# keyBoard.net
KiCad netlist of a schematic drawn in EAGLE
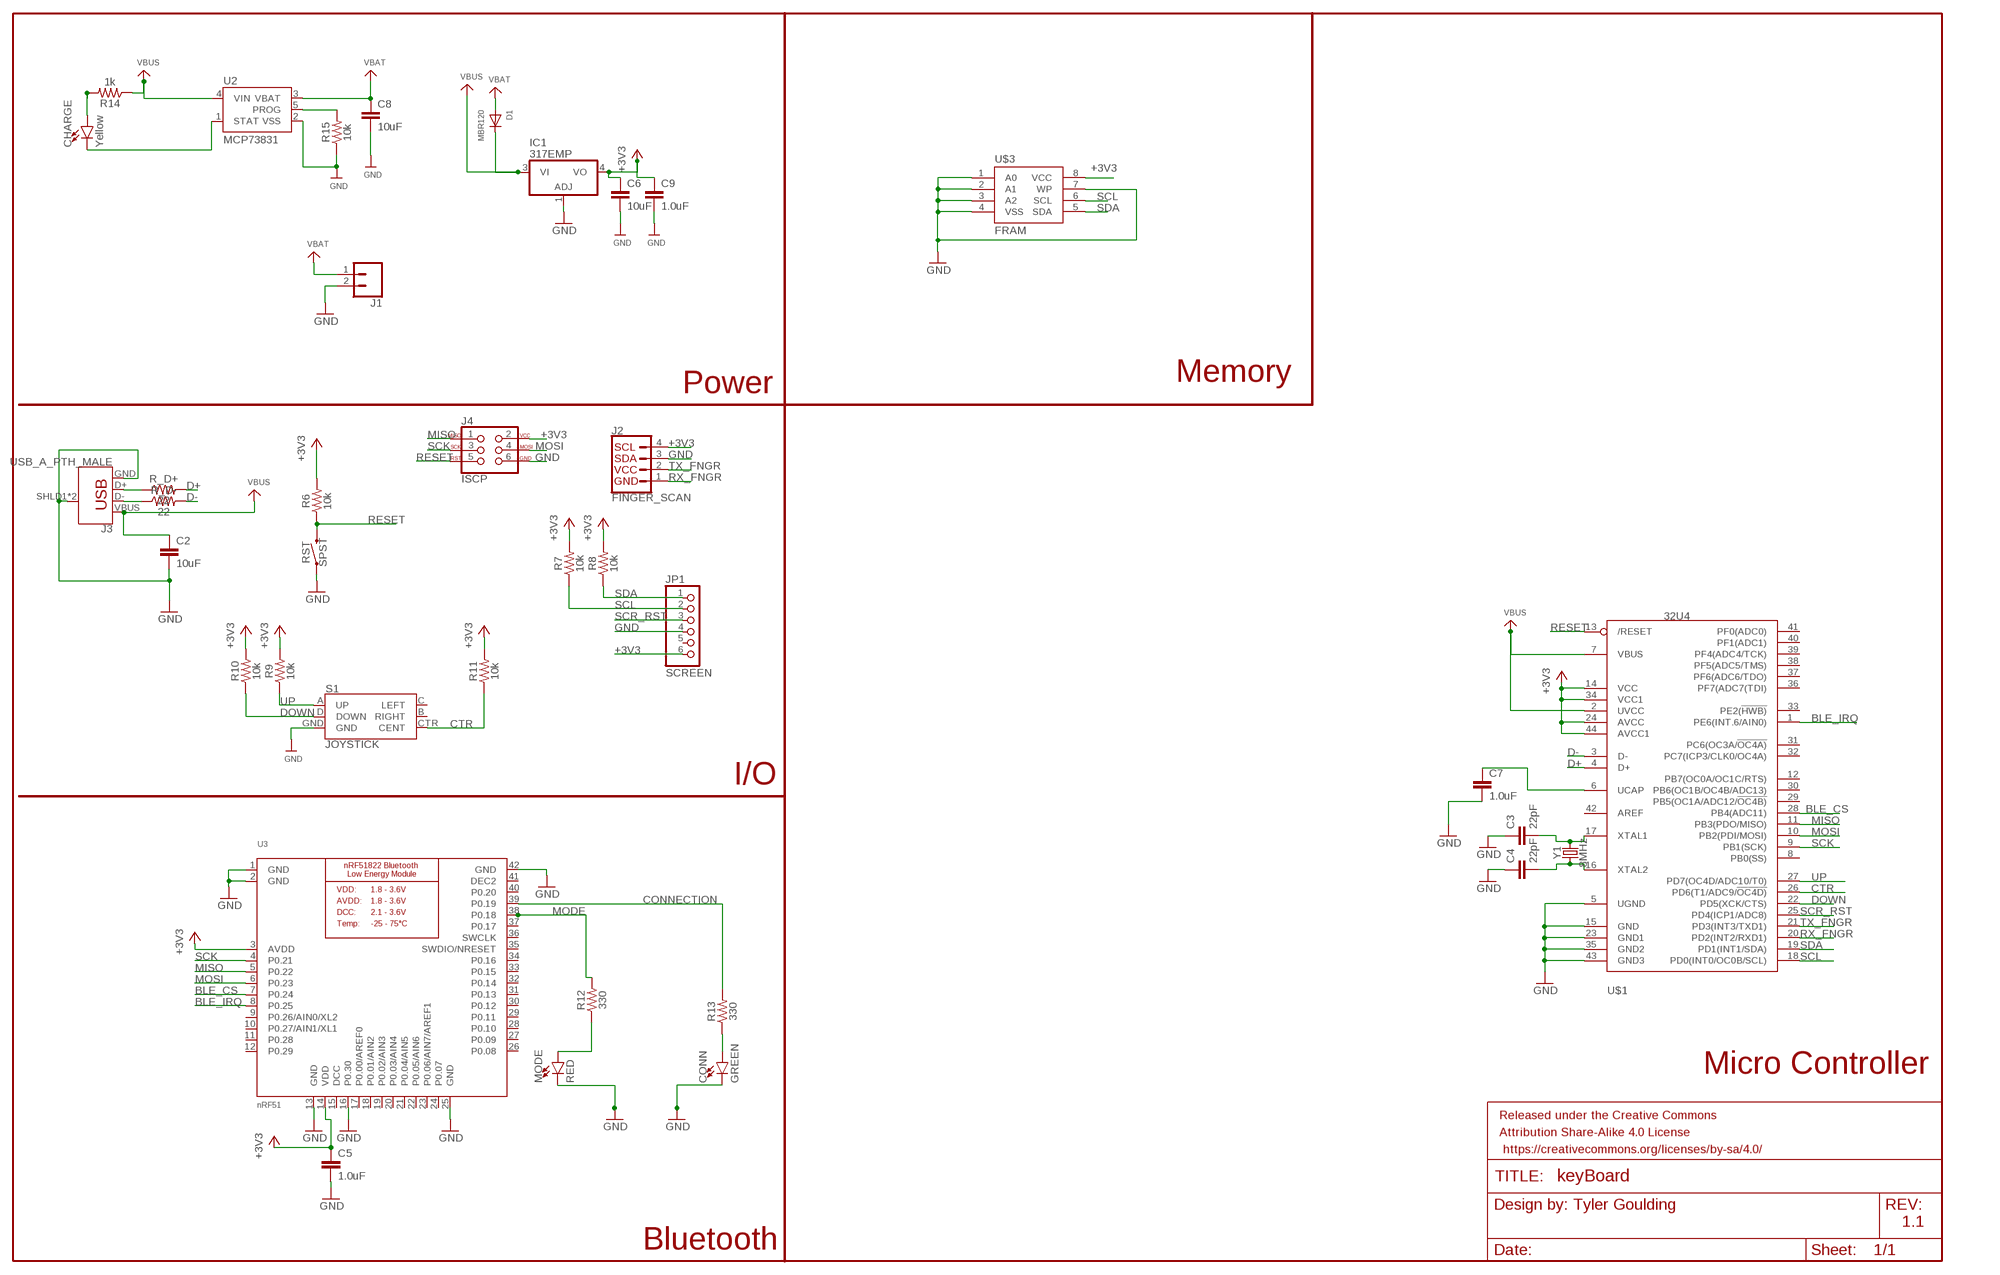
[diagram p0: schematic, sheet 1]

(export (version "E")
  (design (tool "Eeschema 10.0.6"))
  (components
    (comp (ref "C2")
      (value "10uF")
      (footprint "eagle-import:0603")
      (libsource (lib "eagle-import") (part "10UF-0603-6.3V-20%"))
    )
    (comp (ref "C3")
      (value "22pF")
      (footprint "eagle-import:0603")
      (libsource (lib "eagle-import") (part "22PF-0603-50V-5%"))
    )
    (comp (ref "C4")
      (value "22pF")
      (footprint "eagle-import:0603")
      (libsource (lib "eagle-import") (part "22PF-0603-50V-5%"))
    )
    (comp (ref "C5")
      (value "1.0uF")
      (footprint "eagle-import:0603")
      (libsource (lib "eagle-import") (part "1.0UF-0603-16V-10%"))
    )
    (comp (ref "C6")
      (value "10uF")
      (footprint "eagle-import:0603")
      (libsource (lib "eagle-import") (part "10UF-0603-6.3V-20%"))
    )
    (comp (ref "C7")
      (value "1.0uF")
      (footprint "eagle-import:0603")
      (libsource (lib "eagle-import") (part "1.0UF-0603-16V-10%"))
    )
    (comp (ref "C8")
      (value "10uF")
      (footprint "eagle-import:0603")
      (libsource (lib "eagle-import") (part "10UF-0603-6.3V-20%"))
    )
    (comp (ref "C9")
      (value "1.0uF")
      (footprint "eagle-import:0603")
      (libsource (lib "eagle-import") (part "1.0UF-0603-16V-10%"))
    )
    (comp (ref "CHARGE")
      (value "Yellow")
      (footprint "eagle-import:LED-0603")
      (libsource (lib "eagle-import") (part "LED-YELLOW0603"))
    )
    (comp (ref "CONN")
      (value "GREEN")
      (footprint "eagle-import:LED-0603")
      (libsource (lib "eagle-import") (part "LED-GREEN0603"))
    )
    (comp (ref "D1")
      (value "MBR120")
      (footprint "eagle-import:SOD-123FL")
      (libsource (lib "eagle-import") (part "DIODE_SOD-123FL"))
    )
    (comp (ref "FRAME1")
      (value "FRAME-LEDGER")
      (footprint "eagle-import:CREATIVE_COMMONS")
      (libsource (lib "eagle-import") (part "FRAME-LEDGER"))
    )
    (comp (ref "IC1")
      (value "317EMP")
      (footprint "eagle-import:SOT223")
      (libsource (lib "eagle-import") (part "317EMP"))
    )
    (comp (ref "J1")
      (value "CONN_02JST-PTH-2")
      (footprint "eagle-import:JST-2-PTH")
      (libsource (lib "eagle-import") (part "CONN_02JST-PTH-2"))
    )
    (comp (ref "J2")
      (value "FINGER_SCAN")
      (footprint "eagle-import:1X04_1MM_RA")
      (libsource (lib "eagle-import") (part "QWIIC_CONNECTORJS-1MM"))
    )
    (comp (ref "J3")
      (value "USB_A_PTH_MALE")
      (footprint "eagle-import:USB-A-H")
      (libsource (lib "eagle-import") (part "USB_A_PTH_MALE"))
    )
    (comp (ref "J4")
      (value "ISCP")
      (footprint "eagle-import:2X3-NS")
      (libsource (lib "eagle-import") (part "AVR_SPI_PROG_3X2NS"))
    )
    (comp (ref "JP1")
      (value "SCREEN")
      (footprint "eagle-import:1X06_ROUND")
      (libsource (lib "eagle-import") (part "HEADER-1X6ROUND"))
    )
    (comp (ref "MODE")
      (value "RED")
      (footprint "eagle-import:LED-0603")
      (libsource (lib "eagle-import") (part "LED-RED0603"))
    )
    (comp (ref "R6")
      (value "10k")
      (footprint "eagle-import:0603")
      (libsource (lib "eagle-import") (part "10KOHM-0603-1/10W-1%"))
    )
    (comp (ref "R7")
      (value "10k")
      (footprint "eagle-import:0603")
      (libsource (lib "eagle-import") (part "10KOHM-0603-1/10W-1%"))
    )
    (comp (ref "R8")
      (value "10k")
      (footprint "eagle-import:0603")
      (libsource (lib "eagle-import") (part "10KOHM-0603-1/10W-1%"))
    )
    (comp (ref "R9")
      (value "10k")
      (footprint "eagle-import:0603")
      (libsource (lib "eagle-import") (part "10KOHM-0603-1/10W-1%"))
    )
    (comp (ref "R10")
      (value "10k")
      (footprint "eagle-import:0603")
      (libsource (lib "eagle-import") (part "10KOHM-0603-1/10W-1%"))
    )
    (comp (ref "R11")
      (value "10k")
      (footprint "eagle-import:0603")
      (libsource (lib "eagle-import") (part "10KOHM-0603-1/10W-1%"))
    )
    (comp (ref "R12")
      (value "330")
      (footprint "eagle-import:0603")
      (libsource (lib "eagle-import") (part "330OHM-0603-1/10W-1%"))
    )
    (comp (ref "R13")
      (value "330")
      (footprint "eagle-import:0603")
      (libsource (lib "eagle-import") (part "330OHM-0603-1/10W-1%"))
    )
    (comp (ref "R14")
      (value "1k")
      (footprint "eagle-import:0603")
      (libsource (lib "eagle-import") (part "1KOHM-0603-1/10W-1%"))
    )
    (comp (ref "R15")
      (value "10k")
      (footprint "eagle-import:0603")
      (libsource (lib "eagle-import") (part "10KOHM-0603-1/10W-1%"))
    )
    (comp (ref "RST")
      (value "SPST")
      (footprint "eagle-import:TACTILE_SWITCH_SMD_4.5MM")
      (libsource (lib "eagle-import") (part "MOMENTARY-SWITCH-SPST-SMD-4.5MM"))
    )
    (comp (ref "R_D+")
      (value "22")
      (footprint "eagle-import:0603")
      (libsource (lib "eagle-import") (part "22OHM-0603-1/10W-1%"))
    )
    (comp (ref "R_D-")
      (value "22")
      (footprint "eagle-import:0603")
      (libsource (lib "eagle-import") (part "22OHM-0603-1/10W-1%"))
    )
    (comp (ref "S1")
      (value "JOYSTICK")
      (footprint "eagle-import:JOYSTICK_MINI")
      (libsource (lib "eagle-import") (part "JOYSTICK_MINI"))
    )
    (comp (ref "U$1")
      (value "32U4")
      (footprint "eagle-import:TQFP44")
      (libsource (lib "eagle-import") (part "ATMEGA32U4-AU"))
    )
    (comp (ref "U$3")
      (value "FRAM")
      (footprint "eagle-import:SOIC8")
      (libsource (lib "eagle-import") (part "FRAM"))
    )
    (comp (ref "U2")
      (value "MCP73831")
      (footprint "eagle-import:SOT23-5")
      (libsource (lib "eagle-import") (part "MCP73831"))
    )
    (comp (ref "U3")
      (value "nRF51")
      (footprint "eagle-import:BLE_MODULE_RAYTAC_MDBT40")
      (libsource (lib "eagle-import") (part "NRF51822_MODULE_MDBT40"))
    )
    (comp (ref "Y1")
      (value "8MHz")
      (footprint "eagle-import:CRYSTAL-SMD-5X3.2-4PAD")
      (libsource (lib "eagle-import") (part "CRYSTAL-8MHZSMD-5X3.2"))
    )
  )
  (nets
    (net (code "1") (name "+3V3") (class "Default")
      (node (ref "C5") (pin "1") (pinfunction "1_1") (pintype "passive"))
      (node (ref "C6") (pin "1") (pinfunction "1_1") (pintype "passive"))
      (node (ref "C9") (pin "1") (pinfunction "1_1") (pintype "passive"))
      (node (ref "IC1") (pin "4") (pinfunction "VO_4") (pintype "passive"))
      (node (ref "J2") (pin "4") (pinfunction "SCL_4") (pintype "passive"))
      (node (ref "J4") (pin "2") (pinfunction "2_2") (pintype "passive"))
      (node (ref "JP1") (pin "6") (pinfunction "6_6") (pintype "passive"))
      (node (ref "R10") (pin "2") (pinfunction "2_2") (pintype "passive"))
      (node (ref "R11") (pin "2") (pinfunction "2_2") (pintype "passive"))
      (node (ref "R6") (pin "2") (pinfunction "2_2") (pintype "passive"))
      (node (ref "R7") (pin "2") (pinfunction "2_2") (pintype "passive"))
      (node (ref "R8") (pin "2") (pinfunction "2_2") (pintype "passive"))
      (node (ref "R9") (pin "2") (pinfunction "2_2") (pintype "passive"))
      (node (ref "U$1") (pin "14") (pinfunction "VCC_14") (pintype "bidirectional"))
      (node (ref "U$1") (pin "24") (pinfunction "AVCC_24") (pintype "bidirectional"))
      (node (ref "U$1") (pin "34") (pinfunction "VCC1_34") (pintype "bidirectional"))
      (node (ref "U$1") (pin "44") (pinfunction "AVCC1_44") (pintype "bidirectional"))
      (node (ref "U$3") (pin "8") (pinfunction "VCC_8") (pintype "power_in"))
      (node (ref "U3") (pin "14") (pinfunction "VDD_14") (pintype "power_in"))
      (node (ref "U3") (pin "3") (pinfunction "AVDD_3") (pintype "power_in"))
    )
    (net (code "2") (name "/BLE_CS") (class "Default")
      (node (ref "U$1") (pin "28") (pinfunction "PB4(ADC11)_28") (pintype "bidirectional"))
      (node (ref "U3") (pin "7") (pinfunction "P0.24_7") (pintype "bidirectional"))
    )
    (net (code "3") (name "/BLE_IRQ") (class "Default")
      (node (ref "U$1") (pin "1") (pinfunction "PE6(INT.6/AIN0)_1") (pintype "bidirectional"))
      (node (ref "U3") (pin "8") (pinfunction "P0.25_8") (pintype "bidirectional"))
    )
    (net (code "4") (name "/CONNECTION") (class "Default")
      (node (ref "R13") (pin "2") (pinfunction "2_2") (pintype "passive"))
      (node (ref "U3") (pin "39") (pinfunction "P0.19_39") (pintype "bidirectional"))
    )
    (net (code "5") (name "/CTR") (class "Default")
      (node (ref "R11") (pin "1") (pinfunction "1_1") (pintype "passive"))
      (node (ref "S1") (pin "CTR") (pinfunction "CENT_CTR") (pintype "bidirectional"))
      (node (ref "U$1") (pin "26") (pinfunction "PD6(T1/ADC9/~{OC4D})_26") (pintype "bidirectional"))
    )
    (net (code "6") (name "/D+") (class "Default")
      (node (ref "R_D+") (pin "2") (pinfunction "2_2") (pintype "passive"))
      (node (ref "U$1") (pin "4") (pinfunction "D+_4") (pintype "bidirectional"))
    )
    (net (code "7") (name "/D-") (class "Default")
      (node (ref "R_D-") (pin "2") (pinfunction "2_2") (pintype "passive"))
      (node (ref "U$1") (pin "3") (pinfunction "D-_3") (pintype "bidirectional"))
    )
    (net (code "8") (name "/DCC") (class "Default")
      (node (ref "U3") (pin "15") (pinfunction "DCC_15") (pintype "power_in"))
    )
    (net (code "9") (name "/DEC2") (class "Default")
      (node (ref "U3") (pin "41") (pinfunction "DEC2_41") (pintype "power_in"))
    )
    (net (code "10") (name "/DOWN") (class "Default")
      (node (ref "R10") (pin "1") (pinfunction "1_1") (pintype "passive"))
      (node (ref "S1") (pin "D") (pinfunction "DOWN_D") (pintype "bidirectional"))
      (node (ref "U$1") (pin "22") (pinfunction "PD5(XCK/CTS)_22") (pintype "bidirectional"))
    )
    (net (code "11") (name "/MISO") (class "Default")
      (node (ref "J4") (pin "1") (pinfunction "1_1") (pintype "passive"))
      (node (ref "U$1") (pin "11") (pinfunction "PB3(PDO/MISO)_11") (pintype "bidirectional"))
      (node (ref "U3") (pin "5") (pinfunction "P0.22_5") (pintype "bidirectional"))
    )
    (net (code "12") (name "/MODE") (class "Default")
      (node (ref "R12") (pin "2") (pinfunction "2_2") (pintype "passive"))
      (node (ref "U3") (pin "38") (pinfunction "P0.18_38") (pintype "bidirectional"))
    )
    (net (code "13") (name "/MOSI") (class "Default")
      (node (ref "J4") (pin "4") (pinfunction "4_4") (pintype "passive"))
      (node (ref "U$1") (pin "10") (pinfunction "PB2(PDI/MOSI)_10") (pintype "bidirectional"))
      (node (ref "U3") (pin "6") (pinfunction "P0.23_6") (pintype "bidirectional"))
    )
    (net (code "14") (name "/RESET") (class "Default")
      (node (ref "J4") (pin "5") (pinfunction "5_5") (pintype "passive"))
      (node (ref "R6") (pin "1") (pinfunction "1_1") (pintype "passive"))
      (node (ref "RST") (pin "1") (pinfunction "2_1") (pintype "passive"))
      (node (ref "RST") (pin "4") (pinfunction "2_4") (pintype "passive"))
      (node (ref "U$1") (pin "13") (pinfunction "/RESET_13") (pintype "bidirectional"))
    )
    (net (code "15") (name "/RX_FNGR") (class "Default")
      (node (ref "J2") (pin "1") (pinfunction "GND_1") (pintype "power_in"))
      (node (ref "U$1") (pin "20") (pinfunction "PD2(INT2/RXD1)_20") (pintype "bidirectional"))
    )
    (net (code "16") (name "/SCK") (class "Default")
      (node (ref "J4") (pin "3") (pinfunction "3_3") (pintype "passive"))
      (node (ref "U$1") (pin "9") (pinfunction "PB1(SCK)_9") (pintype "bidirectional"))
      (node (ref "U3") (pin "4") (pinfunction "P0.21_4") (pintype "bidirectional"))
    )
    (net (code "17") (name "/SCL") (class "Default")
      (node (ref "JP1") (pin "2") (pinfunction "2_2") (pintype "passive"))
      (node (ref "R7") (pin "1") (pinfunction "1_1") (pintype "passive"))
      (node (ref "U$1") (pin "18") (pinfunction "PD0(INT0/OC0B/SCL)_18") (pintype "bidirectional"))
      (node (ref "U$3") (pin "6") (pinfunction "SCL_6") (pintype "bidirectional"))
    )
    (net (code "18") (name "/SCR_RST") (class "Default")
      (node (ref "JP1") (pin "3") (pinfunction "3_3") (pintype "passive"))
      (node (ref "U$1") (pin "25") (pinfunction "PD4(ICP1/ADC8)_25") (pintype "bidirectional"))
    )
    (net (code "19") (name "/SDA") (class "Default")
      (node (ref "JP1") (pin "1") (pinfunction "1_1") (pintype "passive"))
      (node (ref "R8") (pin "1") (pinfunction "1_1") (pintype "passive"))
      (node (ref "U$1") (pin "19") (pinfunction "PD1(INT1/SDA)_19") (pintype "bidirectional"))
      (node (ref "U$3") (pin "5") (pinfunction "SDA_5") (pintype "bidirectional"))
    )
    (net (code "20") (name "/TX_FNGR") (class "Default")
      (node (ref "J2") (pin "2") (pinfunction "VCC_2") (pintype "power_in"))
      (node (ref "U$1") (pin "21") (pinfunction "PD3(INT3/TXD1)_21") (pintype "bidirectional"))
    )
    (net (code "21") (name "/UP") (class "Default")
      (node (ref "R9") (pin "1") (pinfunction "1_1") (pintype "passive"))
      (node (ref "S1") (pin "A") (pinfunction "UP_A") (pintype "bidirectional"))
      (node (ref "U$1") (pin "27") (pinfunction "PD7(OC4D/ADC10/T0)_27") (pintype "bidirectional"))
    )
    (net (code "22") (name "GND") (class "Default")
      (node (ref "C2") (pin "2") (pinfunction "2_2") (pintype "passive"))
      (node (ref "C3") (pin "1") (pinfunction "1_1") (pintype "passive"))
      (node (ref "C4") (pin "1") (pinfunction "1_1") (pintype "passive"))
      (node (ref "C5") (pin "2") (pinfunction "2_2") (pintype "passive"))
      (node (ref "C6") (pin "2") (pinfunction "2_2") (pintype "passive"))
      (node (ref "C7") (pin "2") (pinfunction "2_2") (pintype "passive"))
      (node (ref "C8") (pin "2") (pinfunction "2_2") (pintype "passive"))
      (node (ref "C9") (pin "2") (pinfunction "2_2") (pintype "passive"))
      (node (ref "CONN") (pin "C") (pinfunction "C_C") (pintype "passive"))
      (node (ref "IC1") (pin "1") (pinfunction "ADJ_1") (pintype "input"))
      (node (ref "J1") (pin "2") (pinfunction "2_2") (pintype "passive"))
      (node (ref "J2") (pin "3") (pinfunction "SDA_3") (pintype "passive"))
      (node (ref "J3") (pin "GND") (pinfunction "GND_GND") (pintype "power_in"))
      (node (ref "J3") (pin "SHLD1") (pinfunction "SHIELD_SHLD1") (pintype "bidirectional"))
      (node (ref "J3") (pin "SHLD2") (pinfunction "SHIELD_SHLD2") (pintype "bidirectional"))
      (node (ref "J4") (pin "6") (pinfunction "6_6") (pintype "passive"))
      (node (ref "JP1") (pin "4") (pinfunction "4_4") (pintype "passive"))
      (node (ref "MODE") (pin "C") (pinfunction "C_C") (pintype "passive"))
      (node (ref "R15") (pin "1") (pinfunction "1_1") (pintype "passive"))
      (node (ref "RST") (pin "2") (pinfunction "1_2") (pintype "passive"))
      (node (ref "RST") (pin "3") (pinfunction "1_3") (pintype "passive"))
      (node (ref "S1") (pin "GND") (pinfunction "GND_GND") (pintype "bidirectional"))
      (node (ref "U$1") (pin "15") (pinfunction "GND_15") (pintype "bidirectional"))
      (node (ref "U$1") (pin "23") (pinfunction "GND1_23") (pintype "bidirectional"))
      (node (ref "U$1") (pin "35") (pinfunction "GND2_35") (pintype "bidirectional"))
      (node (ref "U$1") (pin "43") (pinfunction "GND3_43") (pintype "bidirectional"))
      (node (ref "U$1") (pin "5") (pinfunction "UGND_5") (pintype "bidirectional"))
      (node (ref "U$3") (pin "1") (pinfunction "A0_1") (pintype "bidirectional"))
      (node (ref "U$3") (pin "2") (pinfunction "A1_2") (pintype "bidirectional"))
      (node (ref "U$3") (pin "3") (pinfunction "A2_3") (pintype "bidirectional"))
      (node (ref "U$3") (pin "4") (pinfunction "VSS_4") (pintype "power_in"))
      (node (ref "U$3") (pin "7") (pinfunction "WP_7") (pintype "bidirectional"))
      (node (ref "U2") (pin "2") (pinfunction "VSS_2") (pintype "power_in"))
      (node (ref "U3") (pin "1") (pinfunction "GND_1") (pintype "power_in"))
      (node (ref "U3") (pin "13") (pinfunction "GND_13") (pintype "power_in"))
      (node (ref "U3") (pin "16") (pinfunction "P0.30_16") (pintype "bidirectional"))
      (node (ref "U3") (pin "2") (pinfunction "GND_2") (pintype "power_in"))
      (node (ref "U3") (pin "25") (pinfunction "GND_25") (pintype "power_in"))
      (node (ref "U3") (pin "42") (pinfunction "GND_42") (pintype "power_in"))
    )
    (net (code "23") (name "Net-(CHARGE-PadA)") (class "Default")
      (node (ref "CHARGE") (pin "A") (pinfunction "A_A") (pintype "passive"))
      (node (ref "R14") (pin "2") (pinfunction "2_2") (pintype "passive"))
    )
    (net (code "24") (name "Net-(CONN-PadA)") (class "Default")
      (node (ref "CONN") (pin "A") (pinfunction "A_A") (pintype "passive"))
      (node (ref "R13") (pin "1") (pinfunction "1_1") (pintype "passive"))
    )
    (net (code "25") (name "Net-(J3-PadD+)") (class "Default")
      (node (ref "J3") (pin "D+") (pinfunction "D+_D+") (pintype "bidirectional"))
      (node (ref "R_D+") (pin "1") (pinfunction "1_1") (pintype "passive"))
    )
    (net (code "26") (name "Net-(J3-PadD-)") (class "Default")
      (node (ref "J3") (pin "D-") (pinfunction "D-_D-") (pintype "bidirectional"))
      (node (ref "R_D-") (pin "1") (pinfunction "1_1") (pintype "passive"))
    )
    (net (code "27") (name "Net-(MODE-PadA)") (class "Default")
      (node (ref "MODE") (pin "A") (pinfunction "A_A") (pintype "passive"))
      (node (ref "R12") (pin "1") (pinfunction "1_1") (pintype "passive"))
    )
    (net (code "28") (name "Net-(U$1-UCAP)") (class "Default")
      (node (ref "C7") (pin "1") (pinfunction "1_1") (pintype "passive"))
      (node (ref "U$1") (pin "6") (pinfunction "UCAP_6") (pintype "bidirectional"))
    )
    (net (code "29") (name "Net-(U$1-XTAL1)") (class "Default")
      (node (ref "C3") (pin "2") (pinfunction "2_2") (pintype "passive"))
      (node (ref "U$1") (pin "17") (pinfunction "XTAL1_17") (pintype "bidirectional"))
      (node (ref "Y1") (pin "3") (pinfunction "2_3") (pintype "passive"))
    )
    (net (code "30") (name "Net-(U$1-XTAL2)") (class "Default")
      (node (ref "C4") (pin "2") (pinfunction "2_2") (pintype "passive"))
      (node (ref "U$1") (pin "16") (pinfunction "XTAL2_16") (pintype "bidirectional"))
      (node (ref "Y1") (pin "1") (pinfunction "1_1") (pintype "passive"))
    )
    (net (code "31") (name "Net-(U2-PROG)") (class "Default")
      (node (ref "R15") (pin "2") (pinfunction "2_2") (pintype "passive"))
      (node (ref "U2") (pin "5") (pinfunction "PROG_5") (pintype "input"))
    )
    (net (code "32") (name "Net-(U2-STAT)") (class "Default")
      (node (ref "CHARGE") (pin "C") (pinfunction "C_C") (pintype "passive"))
      (node (ref "U2") (pin "1") (pinfunction "STAT_1") (pintype "output"))
    )
    (net (code "33") (name "VBAT") (class "Default")
      (node (ref "C8") (pin "1") (pinfunction "1_1") (pintype "passive"))
      (node (ref "D1") (pin "A") (pinfunction "A_A") (pintype "passive"))
      (node (ref "J1") (pin "1") (pinfunction "1_1") (pintype "passive"))
      (node (ref "U2") (pin "3") (pinfunction "VBAT_3") (pintype "power_in"))
    )
    (net (code "34") (name "VBUS") (class "Default")
      (node (ref "C2") (pin "1") (pinfunction "1_1") (pintype "passive"))
      (node (ref "D1") (pin "C") (pinfunction "C_C") (pintype "passive"))
      (node (ref "IC1") (pin "3") (pinfunction "VI_3") (pintype "input"))
      (node (ref "J3") (pin "VBUS") (pinfunction "VBUS_VBUS") (pintype "power_in"))
      (node (ref "R14") (pin "1") (pinfunction "1_1") (pintype "passive"))
      (node (ref "U$1") (pin "2") (pinfunction "UVCC_2") (pintype "bidirectional"))
      (node (ref "U$1") (pin "7") (pinfunction "VBUS_7") (pintype "bidirectional"))
      (node (ref "U2") (pin "4") (pinfunction "VIN_4") (pintype "power_in"))
    )
    (net (code "35") (name "unconnected-(JP1-Pad5)") (class "Default")
      (node (ref "JP1") (pin "5") (pinfunction "5_5") (pintype "passive"))
    )
    (net (code "36") (name "unconnected-(S1-LEFT-PadC)") (class "Default")
      (node (ref "S1") (pin "C") (pinfunction "LEFT_C") (pintype "bidirectional"))
    )
    (net (code "37") (name "unconnected-(S1-RIGHT-PadB)") (class "Default")
      (node (ref "S1") (pin "B") (pinfunction "RIGHT_B") (pintype "bidirectional"))
    )
    (net (code "38") (name "unconnected-(U$1-AREF-Pad42)") (class "Default")
      (node (ref "U$1") (pin "42") (pinfunction "AREF_42") (pintype "bidirectional"))
    )
    (net (code "39") (name "unconnected-(U$1-PB0(SS)-Pad8)") (class "Default")
      (node (ref "U$1") (pin "8") (pinfunction "PB0(SS)_8") (pintype "bidirectional"))
    )
    (net (code "40") (name "unconnected-(U$1-PB5(OC1A{slash}ADC12{slash}~{OC4B})-Pad29)") (class "Default")
      (node (ref "U$1") (pin "29") (pinfunction "PB5(OC1A/ADC12/~{OC4B})_29") (pintype "bidirectional"))
    )
    (net (code "41") (name "unconnected-(U$1-PB6(OC1B{slash}OC4B{slash}ADC13)-Pad30)") (class "Default")
      (node (ref "U$1") (pin "30") (pinfunction "PB6(OC1B/OC4B/ADC13)_30") (pintype "bidirectional"))
    )
    (net (code "42") (name "unconnected-(U$1-PB7(OC0A{slash}OC1C{slash}RTS)-Pad12)") (class "Default")
      (node (ref "U$1") (pin "12") (pinfunction "PB7(OC0A/OC1C/RTS)_12") (pintype "bidirectional"))
    )
    (net (code "43") (name "unconnected-(U$1-PC6(OC3A{slash}~{OC4A})-Pad31)") (class "Default")
      (node (ref "U$1") (pin "31") (pinfunction "PC6(OC3A/~{OC4A})_31") (pintype "bidirectional"))
    )
    (net (code "44") (name "unconnected-(U$1-PC7(ICP3{slash}CLK0{slash}OC4A)-Pad32)") (class "Default")
      (node (ref "U$1") (pin "32") (pinfunction "PC7(ICP3/CLK0/OC4A)_32") (pintype "bidirectional"))
    )
    (net (code "45") (name "unconnected-(U$1-PE2(~{HWB})-Pad33)") (class "Default")
      (node (ref "U$1") (pin "33") (pinfunction "PE2(~{HWB})_33") (pintype "bidirectional"))
    )
    (net (code "46") (name "unconnected-(U$1-PF0(ADC0)-Pad41)") (class "Default")
      (node (ref "U$1") (pin "41") (pinfunction "PF0(ADC0)_41") (pintype "bidirectional"))
    )
    (net (code "47") (name "unconnected-(U$1-PF1(ADC1)-Pad40)") (class "Default")
      (node (ref "U$1") (pin "40") (pinfunction "PF1(ADC1)_40") (pintype "bidirectional"))
    )
    (net (code "48") (name "unconnected-(U$1-PF4(ADC4{slash}TCK)-Pad39)") (class "Default")
      (node (ref "U$1") (pin "39") (pinfunction "PF4(ADC4/TCK)_39") (pintype "bidirectional"))
    )
    (net (code "49") (name "unconnected-(U$1-PF5(ADC5{slash}TMS)-Pad38)") (class "Default")
      (node (ref "U$1") (pin "38") (pinfunction "PF5(ADC5/TMS)_38") (pintype "bidirectional"))
    )
    (net (code "50") (name "unconnected-(U$1-PF6(ADC6{slash}TDO)-Pad37)") (class "Default")
      (node (ref "U$1") (pin "37") (pinfunction "PF6(ADC6/TDO)_37") (pintype "bidirectional"))
    )
    (net (code "51") (name "unconnected-(U$1-PF7(ADC7(TDI)-Pad36)") (class "Default")
      (node (ref "U$1") (pin "36") (pinfunction "PF7(ADC7(TDI)_36") (pintype "bidirectional"))
    )
    (net (code "52") (name "unconnected-(U3-P0.00{slash}AREF0-Pad17)") (class "Default")
      (node (ref "U3") (pin "17") (pinfunction "P0.00/AREF0_17") (pintype "bidirectional"))
    )
    (net (code "53") (name "unconnected-(U3-P0.01{slash}AIN2-Pad18)") (class "Default")
      (node (ref "U3") (pin "18") (pinfunction "P0.01/AIN2_18") (pintype "bidirectional"))
    )
    (net (code "54") (name "unconnected-(U3-P0.02{slash}AIN3-Pad19)") (class "Default")
      (node (ref "U3") (pin "19") (pinfunction "P0.02/AIN3_19") (pintype "bidirectional"))
    )
    (net (code "55") (name "unconnected-(U3-P0.03{slash}AIN4-Pad20)") (class "Default")
      (node (ref "U3") (pin "20") (pinfunction "P0.03/AIN4_20") (pintype "bidirectional"))
    )
    (net (code "56") (name "unconnected-(U3-P0.04{slash}AIN5-Pad21)") (class "Default")
      (node (ref "U3") (pin "21") (pinfunction "P0.04/AIN5_21") (pintype "bidirectional"))
    )
    (net (code "57") (name "unconnected-(U3-P0.05{slash}AIN6-Pad22)") (class "Default")
      (node (ref "U3") (pin "22") (pinfunction "P0.05/AIN6_22") (pintype "bidirectional"))
    )
    (net (code "58") (name "unconnected-(U3-P0.06{slash}AIN7{slash}AREF1-Pad23)") (class "Default")
      (node (ref "U3") (pin "23") (pinfunction "P0.06/AIN7/AREF1_23") (pintype "bidirectional"))
    )
    (net (code "59") (name "unconnected-(U3-P0.07-Pad24)") (class "Default")
      (node (ref "U3") (pin "24") (pinfunction "P0.07_24") (pintype "bidirectional"))
    )
    (net (code "60") (name "unconnected-(U3-P0.08-Pad26)") (class "Default")
      (node (ref "U3") (pin "26") (pinfunction "P0.08_26") (pintype "bidirectional"))
    )
    (net (code "61") (name "unconnected-(U3-P0.09-Pad27)") (class "Default")
      (node (ref "U3") (pin "27") (pinfunction "P0.09_27") (pintype "bidirectional"))
    )
    (net (code "62") (name "unconnected-(U3-P0.10-Pad28)") (class "Default")
      (node (ref "U3") (pin "28") (pinfunction "P0.10_28") (pintype "bidirectional"))
    )
    (net (code "63") (name "unconnected-(U3-P0.11-Pad29)") (class "Default")
      (node (ref "U3") (pin "29") (pinfunction "P0.11_29") (pintype "bidirectional"))
    )
    (net (code "64") (name "unconnected-(U3-P0.12-Pad30)") (class "Default")
      (node (ref "U3") (pin "30") (pinfunction "P0.12_30") (pintype "bidirectional"))
    )
    (net (code "65") (name "unconnected-(U3-P0.13-Pad31)") (class "Default")
      (node (ref "U3") (pin "31") (pinfunction "P0.13_31") (pintype "bidirectional"))
    )
    (net (code "66") (name "unconnected-(U3-P0.14-Pad32)") (class "Default")
      (node (ref "U3") (pin "32") (pinfunction "P0.14_32") (pintype "bidirectional"))
    )
    (net (code "67") (name "unconnected-(U3-P0.15-Pad33)") (class "Default")
      (node (ref "U3") (pin "33") (pinfunction "P0.15_33") (pintype "bidirectional"))
    )
    (net (code "68") (name "unconnected-(U3-P0.16-Pad34)") (class "Default")
      (node (ref "U3") (pin "34") (pinfunction "P0.16_34") (pintype "bidirectional"))
    )
    (net (code "69") (name "unconnected-(U3-P0.17-Pad37)") (class "Default")
      (node (ref "U3") (pin "37") (pinfunction "P0.17_37") (pintype "bidirectional"))
    )
    (net (code "70") (name "unconnected-(U3-P0.20-Pad40)") (class "Default")
      (node (ref "U3") (pin "40") (pinfunction "P0.20_40") (pintype "bidirectional"))
    )
    (net (code "71") (name "unconnected-(U3-P0.26{slash}AIN0{slash}XL2-Pad9)") (class "Default")
      (node (ref "U3") (pin "9") (pinfunction "P0.26/AIN0/XL2_9") (pintype "bidirectional"))
    )
    (net (code "72") (name "unconnected-(U3-P0.27{slash}AIN1{slash}XL1-Pad10)") (class "Default")
      (node (ref "U3") (pin "10") (pinfunction "P0.27/AIN1/XL1_10") (pintype "bidirectional"))
    )
    (net (code "73") (name "unconnected-(U3-P0.28-Pad11)") (class "Default")
      (node (ref "U3") (pin "11") (pinfunction "P0.28_11") (pintype "bidirectional"))
    )
    (net (code "74") (name "unconnected-(U3-P0.29-Pad12)") (class "Default")
      (node (ref "U3") (pin "12") (pinfunction "P0.29_12") (pintype "bidirectional"))
    )
    (net (code "75") (name "unconnected-(U3-SWCLK-Pad36)") (class "Default")
      (node (ref "U3") (pin "36") (pinfunction "SWCLK_36") (pintype "bidirectional"))
    )
    (net (code "76") (name "unconnected-(U3-SWDIO{slash}NRESET-Pad35)") (class "Default")
      (node (ref "U3") (pin "35") (pinfunction "SWDIO/NRESET_35") (pintype "bidirectional"))
    )
  )
)
